# uhf_real_control_v2.net
KiCad netlist of a schematic drawn in EAGLE
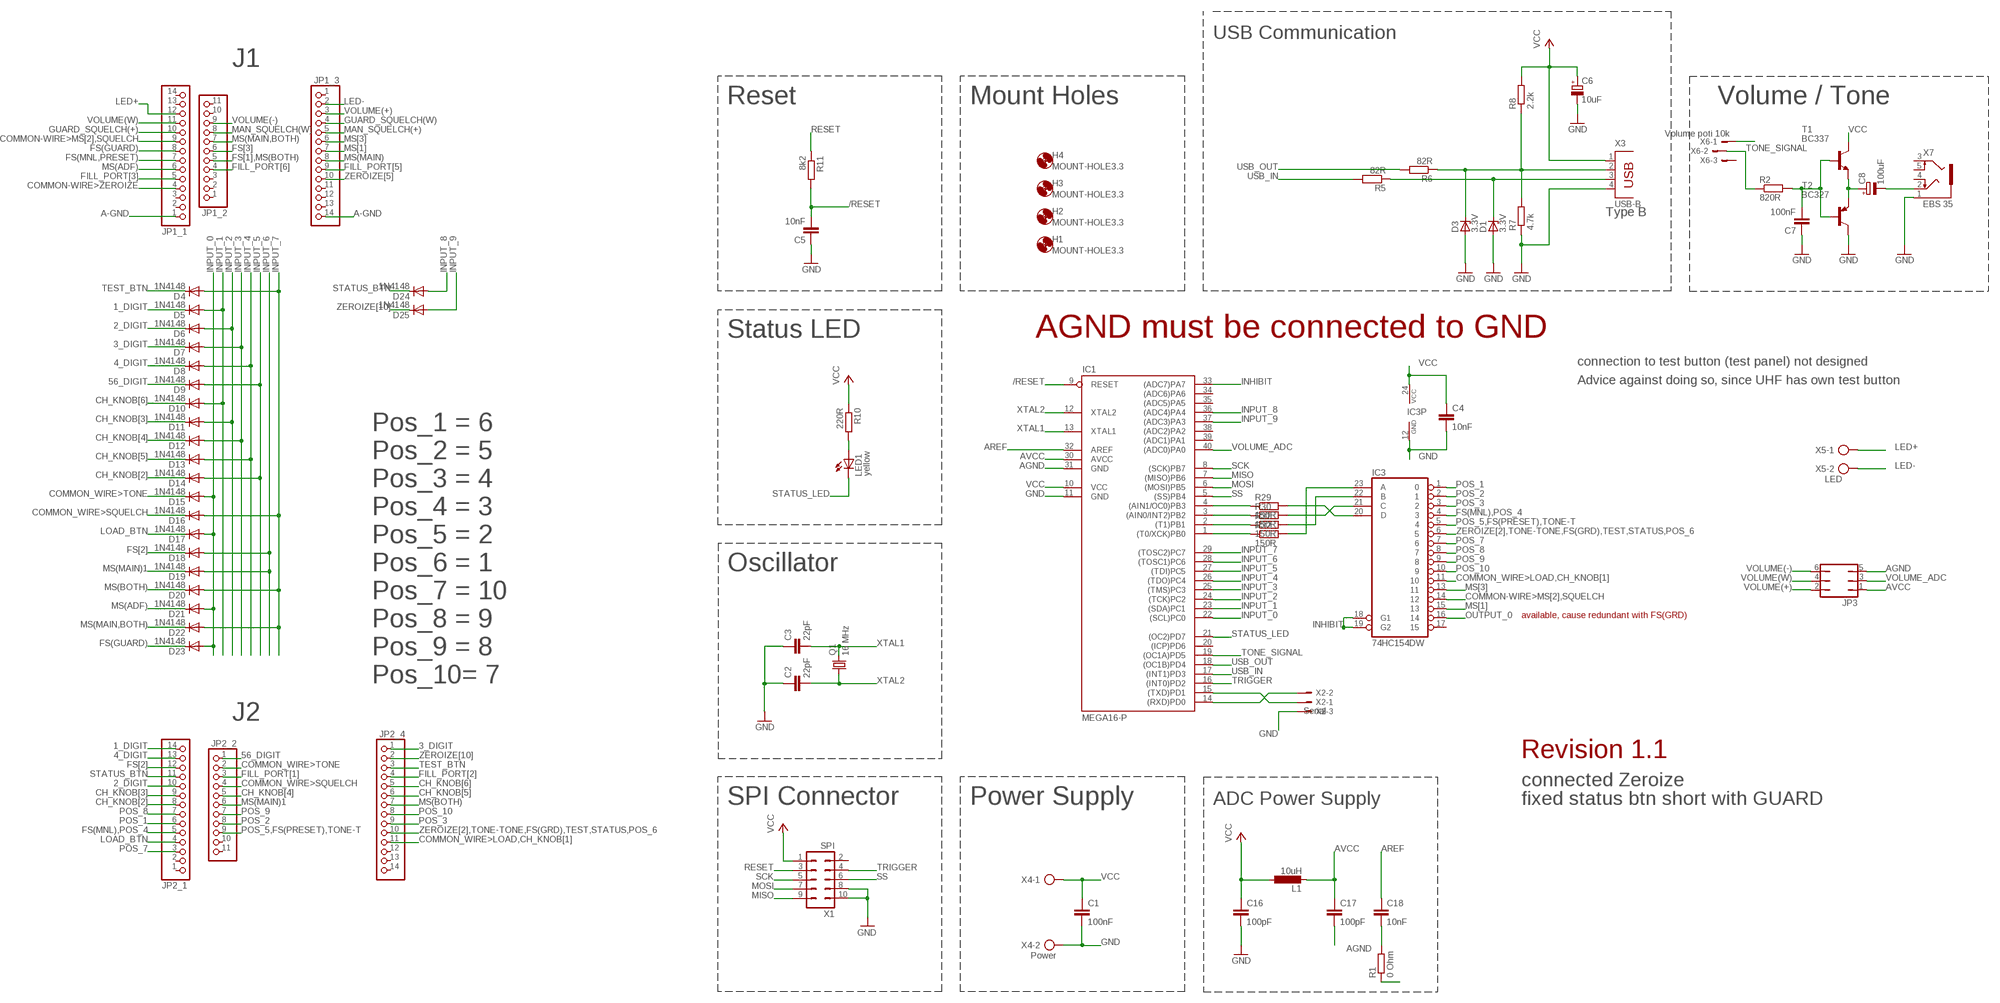
[diagram p0: schematic, sheet 1]

(export (version "E")
  (design (tool "Eeschema 10.0.6"))
  (components
    (comp (ref "C1")
      (value "100nF")
      (footprint "eagle-import:C050-024X044")
      (libsource (lib "eagle-import") (part "C-EU050-024X044"))
    )
    (comp (ref "C2")
      (value "22pF")
      (footprint "eagle-import:C025-025X050")
      (libsource (lib "eagle-import") (part "C-EU025-025X050"))
    )
    (comp (ref "C3")
      (value "22pF")
      (footprint "eagle-import:C025-025X050")
      (libsource (lib "eagle-import") (part "C-EU025-025X050"))
    )
    (comp (ref "C4")
      (value "10nF")
      (footprint "eagle-import:C025-025X050")
      (libsource (lib "eagle-import") (part "C-EU025-025X050"))
    )
    (comp (ref "C5")
      (value "10nF")
      (footprint "eagle-import:C025-025X050")
      (libsource (lib "eagle-import") (part "C-EU025-025X050"))
    )
    (comp (ref "C6")
      (value "10uF")
      (footprint "eagle-import:E2,5-6")
      (libsource (lib "eagle-import") (part "CPOL-EUE2.5-6"))
    )
    (comp (ref "C7")
      (value "100nF")
      (footprint "eagle-import:C050-024X044")
      (libsource (lib "eagle-import") (part "C-EU050-024X044"))
    )
    (comp (ref "C8")
      (value "100uF")
      (footprint "eagle-import:E2,5-6")
      (libsource (lib "eagle-import") (part "CPOL-EUE2.5-6"))
    )
    (comp (ref "C16")
      (value "100pF")
      (footprint "eagle-import:C025-025X050")
      (libsource (lib "eagle-import") (part "C-EU025-025X050"))
    )
    (comp (ref "C17")
      (value "100pF")
      (footprint "eagle-import:C025-025X050")
      (libsource (lib "eagle-import") (part "C-EU025-025X050"))
    )
    (comp (ref "C18")
      (value "10nF")
      (footprint "eagle-import:C025-025X050")
      (libsource (lib "eagle-import") (part "C-EU025-025X050"))
    )
    (comp (ref "D1")
      (value "3.3V")
      (footprint "eagle-import:DO35Z10")
      (libsource (lib "eagle-import") (part "ZENER-DIODEDO35Z10"))
    )
    (comp (ref "D3")
      (value "3.3V")
      (footprint "eagle-import:DO35Z10")
      (libsource (lib "eagle-import") (part "ZENER-DIODEDO35Z10"))
    )
    (comp (ref "D4")
      (value "1N4148")
      (footprint "eagle-import:MINIMELF")
      (libsource (lib "eagle-import") (part "DIODE-MINIMELF"))
    )
    (comp (ref "D5")
      (value "1N4148")
      (footprint "eagle-import:MINIMELF")
      (libsource (lib "eagle-import") (part "DIODE-MINIMELF"))
    )
    (comp (ref "D6")
      (value "1N4148")
      (footprint "eagle-import:MINIMELF")
      (libsource (lib "eagle-import") (part "DIODE-MINIMELF"))
    )
    (comp (ref "D7")
      (value "1N4148")
      (footprint "eagle-import:MINIMELF")
      (libsource (lib "eagle-import") (part "DIODE-MINIMELF"))
    )
    (comp (ref "D8")
      (value "1N4148")
      (footprint "eagle-import:MINIMELF")
      (libsource (lib "eagle-import") (part "DIODE-MINIMELF"))
    )
    (comp (ref "D9")
      (value "1N4148")
      (footprint "eagle-import:MINIMELF")
      (libsource (lib "eagle-import") (part "DIODE-MINIMELF"))
    )
    (comp (ref "D10")
      (value "1N4148")
      (footprint "eagle-import:MINIMELF")
      (libsource (lib "eagle-import") (part "DIODE-MINIMELF"))
    )
    (comp (ref "D11")
      (value "1N4148")
      (footprint "eagle-import:MINIMELF")
      (libsource (lib "eagle-import") (part "DIODE-MINIMELF"))
    )
    (comp (ref "D12")
      (value "1N4148")
      (footprint "eagle-import:MINIMELF")
      (libsource (lib "eagle-import") (part "DIODE-MINIMELF"))
    )
    (comp (ref "D13")
      (value "1N4148")
      (footprint "eagle-import:MINIMELF")
      (libsource (lib "eagle-import") (part "DIODE-MINIMELF"))
    )
    (comp (ref "D14")
      (value "1N4148")
      (footprint "eagle-import:MINIMELF")
      (libsource (lib "eagle-import") (part "DIODE-MINIMELF"))
    )
    (comp (ref "D15")
      (value "1N4148")
      (footprint "eagle-import:MINIMELF")
      (libsource (lib "eagle-import") (part "DIODE-MINIMELF"))
    )
    (comp (ref "D16")
      (value "1N4148")
      (footprint "eagle-import:MINIMELF")
      (libsource (lib "eagle-import") (part "DIODE-MINIMELF"))
    )
    (comp (ref "D17")
      (value "1N4148")
      (footprint "eagle-import:MINIMELF")
      (libsource (lib "eagle-import") (part "DIODE-MINIMELF"))
    )
    (comp (ref "D18")
      (value "1N4148")
      (footprint "eagle-import:MINIMELF")
      (libsource (lib "eagle-import") (part "DIODE-MINIMELF"))
    )
    (comp (ref "D19")
      (value "1N4148")
      (footprint "eagle-import:MINIMELF")
      (libsource (lib "eagle-import") (part "DIODE-MINIMELF"))
    )
    (comp (ref "D20")
      (value "1N4148")
      (footprint "eagle-import:MINIMELF")
      (libsource (lib "eagle-import") (part "DIODE-MINIMELF"))
    )
    (comp (ref "D21")
      (value "1N4148")
      (footprint "eagle-import:MINIMELF")
      (libsource (lib "eagle-import") (part "DIODE-MINIMELF"))
    )
    (comp (ref "D22")
      (value "1N4148")
      (footprint "eagle-import:MINIMELF")
      (libsource (lib "eagle-import") (part "DIODE-MINIMELF"))
    )
    (comp (ref "D23")
      (value "1N4148")
      (footprint "eagle-import:MINIMELF")
      (libsource (lib "eagle-import") (part "DIODE-MINIMELF"))
    )
    (comp (ref "D24")
      (value "1N4148")
      (footprint "eagle-import:MINIMELF")
      (libsource (lib "eagle-import") (part "DIODE-MINIMELF"))
    )
    (comp (ref "D25")
      (value "1N4148")
      (footprint "eagle-import:MINIMELF")
      (libsource (lib "eagle-import") (part "DIODE-MINIMELF"))
    )
    (comp (ref "H1")
      (value "MOUNT-HOLE3.3")
      (footprint "eagle-import:3,3")
      (libsource (lib "eagle-import") (part "MOUNT-HOLE3.3"))
    )
    (comp (ref "H2")
      (value "MOUNT-HOLE3.3")
      (footprint "eagle-import:3,3")
      (libsource (lib "eagle-import") (part "MOUNT-HOLE3.3"))
    )
    (comp (ref "H3")
      (value "MOUNT-HOLE3.3")
      (footprint "eagle-import:3,3")
      (libsource (lib "eagle-import") (part "MOUNT-HOLE3.3"))
    )
    (comp (ref "H4")
      (value "MOUNT-HOLE3.3")
      (footprint "eagle-import:3,3")
      (libsource (lib "eagle-import") (part "MOUNT-HOLE3.3"))
    )
    (comp (ref "IC1")
      (value "MEGA16-P")
      (footprint "eagle-import:DIL40")
      (libsource (lib "eagle-import") (part "MEGA16-P"))
    )
    (comp (ref "IC3")
      (value "74HC154DW")
      (footprint "eagle-import:SO24W")
      (libsource (lib "eagle-import") (part "74154DWHC"))
    )
    (comp (ref "JP1_1")
      (value "PINHD-1X14")
      (footprint "eagle-import:1X14")
      (libsource (lib "eagle-import") (part "PINHD-1X14"))
    )
    (comp (ref "JP1_2")
      (value "PINHD-1X11")
      (footprint "eagle-import:1X11")
      (libsource (lib "eagle-import") (part "PINHD-1X11"))
    )
    (comp (ref "JP1_3")
      (value "PINHD-1X14")
      (footprint "eagle-import:1X14")
      (libsource (lib "eagle-import") (part "PINHD-1X14"))
    )
    (comp (ref "JP2_1")
      (value "PINHD-1X14")
      (footprint "eagle-import:1X14")
      (libsource (lib "eagle-import") (part "PINHD-1X14"))
    )
    (comp (ref "JP2_2")
      (value "PINHD-1X11")
      (footprint "eagle-import:1X11")
      (libsource (lib "eagle-import") (part "PINHD-1X11"))
    )
    (comp (ref "JP2_4")
      (value "PINHD-1X14")
      (footprint "eagle-import:1X14")
      (libsource (lib "eagle-import") (part "PINHD-1X14"))
    )
    (comp (ref "JP3")
      (value "JP3Q")
      (footprint "eagle-import:JP3Q")
      (libsource (lib "eagle-import") (part "JP3Q"))
    )
    (comp (ref "L1")
      (value "10uH")
      (footprint "eagle-import:2200-15.24")
      (libsource (lib "eagle-import") (part "L-EU2200-15.24"))
    )
    (comp (ref "LED1")
      (value "yellow")
      (footprint "eagle-import:CHIPLED_1206")
      (libsource (lib "eagle-import") (part "LEDCHIPLED_1206"))
    )
    (comp (ref "Q1")
      (value "16 MHz")
      (footprint "eagle-import:HC18U-V")
      (libsource (lib "eagle-import") (part "CRYSTALHC18U-V"))
    )
    (comp (ref "R1")
      (value "0 Ohm")
      (footprint "eagle-import:R0805")
      (libsource (lib "eagle-import") (part "R-EU_R0805"))
    )
    (comp (ref "R2")
      (value "820R")
      (footprint "eagle-import:0207_12")
      (libsource (lib "eagle-import") (part "R-EU_0207/12"))
    )
    (comp (ref "R5")
      (value "82R")
      (footprint "eagle-import:R0805")
      (libsource (lib "eagle-import") (part "R-EU_R0805"))
    )
    (comp (ref "R6")
      (value "82R")
      (footprint "eagle-import:R0805")
      (libsource (lib "eagle-import") (part "R-EU_R0805"))
    )
    (comp (ref "R7")
      (value "4.7k")
      (footprint "eagle-import:R0805")
      (libsource (lib "eagle-import") (part "R-EU_R0805"))
    )
    (comp (ref "R8")
      (value "2.2k")
      (footprint "eagle-import:R0805")
      (libsource (lib "eagle-import") (part "R-EU_R0805"))
    )
    (comp (ref "R10")
      (value "220R")
      (footprint "eagle-import:R0805")
      (libsource (lib "eagle-import") (part "R-EU_R0805"))
    )
    (comp (ref "R11")
      (value "8k2")
      (footprint "eagle-import:M0805")
      (libsource (lib "eagle-import") (part "R-EU_M0805"))
    )
    (comp (ref "R29")
      (value "150R")
      (footprint "eagle-import:M0805")
      (libsource (lib "eagle-import") (part "R-EU_M0805"))
    )
    (comp (ref "R30")
      (value "150R")
      (footprint "eagle-import:M0805")
      (libsource (lib "eagle-import") (part "R-EU_M0805"))
    )
    (comp (ref "R31")
      (value "150R")
      (footprint "eagle-import:M0805")
      (libsource (lib "eagle-import") (part "R-EU_M0805"))
    )
    (comp (ref "R32")
      (value "150R")
      (footprint "eagle-import:M0805")
      (libsource (lib "eagle-import") (part "R-EU_M0805"))
    )
    (comp (ref "T1")
      (value "BC337")
      (footprint "eagle-import:TO92-EBC")
      (libsource (lib "eagle-import") (part "-NPN-TO92-EBCBC337-25"))
    )
    (comp (ref "T2")
      (value "BC327")
      (footprint "eagle-import:TO92-EBC")
      (libsource (lib "eagle-import") (part "-PNP-TO92-EBCBC327-25"))
    )
    (comp (ref "X1")
      (value "SPI")
      (footprint "eagle-import:ML10")
      (libsource (lib "eagle-import") (part "ML10"))
    )
    (comp (ref "X2")
      (value "Serial")
      (footprint "eagle-import:22-23-2031")
      (fields (field (name "MF") "MOLEX") (field (name "MPN") "22-23-2031"))
      (libsource (lib "eagle-import") (part "22-23-2031"))
    )
    (comp (ref "X3")
      (value "USB-B")
      (footprint "eagle-import:PN61729")
      (libsource (lib "eagle-import") (part "PN61729"))
    )
    (comp (ref "X4")
      (value "Power")
      (footprint "eagle-import:AK500_2")
      (libsource (lib "eagle-import") (part "AK500/2"))
    )
    (comp (ref "X5")
      (value "LED")
      (footprint "eagle-import:AK500_2")
      (libsource (lib "eagle-import") (part "AK500/2"))
    )
    (comp (ref "X6")
      (value "Volume poti 10k")
      (footprint "eagle-import:22-23-2031")
      (fields (field (name "MF") "MOLEX") (field (name "MPN") "22-23-2031"))
      (libsource (lib "eagle-import") (part "22-23-2031"))
    )
    (comp (ref "X7")
      (value "EBS 35")
      (footprint "eagle-import:1503_09")
      (libsource (lib "eagle-import") (part "1503_09"))
    )
  )
  (nets
    (net (code "1") (name "/1_DIGIT") (class "Default")
      (node (ref "D5") (pin "C") (pinfunction "C_C") (pintype "passive"))
      (node (ref "JP2_1") (pin "14") (pinfunction "14_14") (pintype "passive"))
    )
    (net (code "2") (name "/2_DIGIT") (class "Default")
      (node (ref "D6") (pin "C") (pinfunction "C_C") (pintype "passive"))
      (node (ref "JP2_1") (pin "10") (pinfunction "10_10") (pintype "passive"))
    )
    (net (code "3") (name "/3_DIGIT") (class "Default")
      (node (ref "D7") (pin "C") (pinfunction "C_C") (pintype "passive"))
      (node (ref "JP2_4") (pin "1") (pinfunction "1_1") (pintype "passive"))
    )
    (net (code "4") (name "/4_DIGIT") (class "Default")
      (node (ref "D8") (pin "C") (pinfunction "C_C") (pintype "passive"))
      (node (ref "JP2_1") (pin "13") (pinfunction "13_13") (pintype "passive"))
    )
    (net (code "5") (name "/56_DIGIT") (class "Default")
      (node (ref "D9") (pin "C") (pinfunction "C_C") (pintype "passive"))
      (node (ref "JP2_2") (pin "1") (pinfunction "1_1") (pintype "passive"))
    )
    (net (code "6") (name "/A-GND") (class "Default")
      (node (ref "JP1_1") (pin "1") (pinfunction "1_1") (pintype "passive"))
      (node (ref "JP1_3") (pin "14") (pinfunction "14_14") (pintype "passive"))
    )
    (net (code "7") (name "/AGND") (class "Default")
      (node (ref "C17") (pin "2") (pinfunction "2_2") (pintype "passive"))
      (node (ref "C18") (pin "2") (pinfunction "2_2") (pintype "passive"))
      (node (ref "IC1") (pin "31") (pinfunction "GND_31") (pintype "power_in"))
      (node (ref "JP3") (pin "5") (pinfunction "5_5") (pintype "passive"))
      (node (ref "R1") (pin "2") (pinfunction "2_2") (pintype "passive"))
    )
    (net (code "8") (name "/AREF") (class "Default")
      (node (ref "C18") (pin "1") (pinfunction "1_1") (pintype "passive"))
      (node (ref "IC1") (pin "32") (pinfunction "AREF_32") (pintype "passive"))
    )
    (net (code "9") (name "/AVCC") (class "Default")
      (node (ref "C17") (pin "1") (pinfunction "1_1") (pintype "passive"))
      (node (ref "IC1") (pin "30") (pinfunction "AVCC_30") (pintype "power_in"))
      (node (ref "JP3") (pin "1") (pinfunction "1_1") (pintype "passive"))
      (node (ref "L1") (pin "2") (pinfunction "2_2") (pintype "passive"))
    )
    (net (code "10") (name "/CH_KNOB[2]") (class "Default")
      (node (ref "D14") (pin "C") (pinfunction "C_C") (pintype "passive"))
      (node (ref "JP2_1") (pin "8") (pinfunction "8_8") (pintype "passive"))
    )
    (net (code "11") (name "/CH_KNOB[3]") (class "Default")
      (node (ref "D11") (pin "C") (pinfunction "C_C") (pintype "passive"))
      (node (ref "JP2_1") (pin "9") (pinfunction "9_9") (pintype "passive"))
    )
    (net (code "12") (name "/CH_KNOB[4]") (class "Default")
      (node (ref "D12") (pin "C") (pinfunction "C_C") (pintype "passive"))
      (node (ref "JP2_2") (pin "5") (pinfunction "5_5") (pintype "passive"))
    )
    (net (code "13") (name "/CH_KNOB[5]") (class "Default")
      (node (ref "D13") (pin "C") (pinfunction "C_C") (pintype "passive"))
      (node (ref "JP2_4") (pin "6") (pinfunction "6_6") (pintype "passive"))
    )
    (net (code "14") (name "/CH_KNOB[6]") (class "Default")
      (node (ref "D10") (pin "C") (pinfunction "C_C") (pintype "passive"))
      (node (ref "JP2_4") (pin "5") (pinfunction "5_5") (pintype "passive"))
    )
    (net (code "15") (name "/COMMON-WIRE>MS[2],SQUELCH") (class "Default")
      (node (ref "IC3") (pin "14") (pinfunction "12_14") (pintype "output"))
      (node (ref "JP1_1") (pin "9") (pinfunction "9_9") (pintype "passive"))
    )
    (net (code "16") (name "/COMMON-WIRE>ZEROIZE") (class "Default")
      (node (ref "JP1_1") (pin "4") (pinfunction "4_4") (pintype "passive"))
    )
    (net (code "17") (name "/COMMON_WIRE>LOAD,CH_KNOB[1]") (class "Default")
      (node (ref "IC3") (pin "11") (pinfunction "10_11") (pintype "output"))
      (node (ref "JP2_4") (pin "11") (pinfunction "11_11") (pintype "passive"))
    )
    (net (code "18") (name "/COMMON_WIRE>SQUELCH") (class "Default")
      (node (ref "D16") (pin "C") (pinfunction "C_C") (pintype "passive"))
      (node (ref "JP2_2") (pin "4") (pinfunction "4_4") (pintype "passive"))
    )
    (net (code "19") (name "/COMMON_WIRE>TONE") (class "Default")
      (node (ref "D15") (pin "C") (pinfunction "C_C") (pintype "passive"))
      (node (ref "JP2_2") (pin "2") (pinfunction "2_2") (pintype "passive"))
    )
    (net (code "20") (name "/FILL_PORT[1]") (class "Default")
      (node (ref "JP2_2") (pin "3") (pinfunction "3_3") (pintype "passive"))
    )
    (net (code "21") (name "/FILL_PORT[2]") (class "Default")
      (node (ref "JP2_4") (pin "4") (pinfunction "4_4") (pintype "passive"))
    )
    (net (code "22") (name "/FILL_PORT[3]") (class "Default")
      (node (ref "JP1_1") (pin "5") (pinfunction "5_5") (pintype "passive"))
    )
    (net (code "23") (name "/FILL_PORT[5]") (class "Default")
      (node (ref "JP1_3") (pin "9") (pinfunction "9_9") (pintype "passive"))
    )
    (net (code "24") (name "/FILL_PORT[6]") (class "Default")
      (node (ref "JP1_2") (pin "4") (pinfunction "4_4") (pintype "passive"))
    )
    (net (code "25") (name "/FS(GUARD)") (class "Default")
      (node (ref "D23") (pin "C") (pinfunction "C_C") (pintype "passive"))
      (node (ref "JP1_1") (pin "8") (pinfunction "8_8") (pintype "passive"))
    )
    (net (code "26") (name "/FS(MNL),POS_4") (class "Default")
      (node (ref "IC3") (pin "4") (pinfunction "3_4") (pintype "output"))
      (node (ref "JP2_1") (pin "5") (pinfunction "5_5") (pintype "passive"))
    )
    (net (code "27") (name "/FS(MNL,PRESET)") (class "Default")
      (node (ref "JP1_1") (pin "7") (pinfunction "7_7") (pintype "passive"))
    )
    (net (code "28") (name "/FS[1],MS(BOTH)") (class "Default")
      (node (ref "JP1_2") (pin "5") (pinfunction "5_5") (pintype "passive"))
    )
    (net (code "29") (name "/FS[2]") (class "Default")
      (node (ref "D18") (pin "C") (pinfunction "C_C") (pintype "passive"))
      (node (ref "JP2_1") (pin "12") (pinfunction "12_12") (pintype "passive"))
    )
    (net (code "30") (name "/FS[3]") (class "Default")
      (node (ref "JP1_2") (pin "6") (pinfunction "6_6") (pintype "passive"))
    )
    (net (code "31") (name "/GUARD_SQUELCH(+)") (class "Default")
      (node (ref "JP1_1") (pin "10") (pinfunction "10_10") (pintype "passive"))
    )
    (net (code "32") (name "/GUARD_SQUELCH(W)") (class "Default")
      (node (ref "JP1_3") (pin "4") (pinfunction "4_4") (pintype "passive"))
    )
    (net (code "33") (name "/INHIBIT") (class "Default")
      (node (ref "IC1") (pin "33") (pinfunction "(ADC7)PA7_33") (pintype "bidirectional"))
      (node (ref "IC3") (pin "18") (pinfunction "G1_18") (pintype "input"))
      (node (ref "IC3") (pin "19") (pinfunction "G2_19") (pintype "input"))
    )
    (net (code "34") (name "/INPUT_0") (class "Default")
      (node (ref "D15") (pin "A") (pinfunction "A_A") (pintype "passive"))
      (node (ref "D17") (pin "A") (pinfunction "A_A") (pintype "passive"))
      (node (ref "D21") (pin "A") (pinfunction "A_A") (pintype "passive"))
      (node (ref "D23") (pin "A") (pinfunction "A_A") (pintype "passive"))
      (node (ref "IC1") (pin "22") (pinfunction "(SCL)PC0_22") (pintype "bidirectional"))
    )
    (net (code "35") (name "/INPUT_1") (class "Default")
      (node (ref "D10") (pin "A") (pinfunction "A_A") (pintype "passive"))
      (node (ref "D5") (pin "A") (pinfunction "A_A") (pintype "passive"))
      (node (ref "IC1") (pin "23") (pinfunction "(SDA)PC1_23") (pintype "bidirectional"))
    )
    (net (code "36") (name "/INPUT_2") (class "Default")
      (node (ref "D11") (pin "A") (pinfunction "A_A") (pintype "passive"))
      (node (ref "D6") (pin "A") (pinfunction "A_A") (pintype "passive"))
      (node (ref "IC1") (pin "24") (pinfunction "(TCK)PC2_24") (pintype "bidirectional"))
    )
    (net (code "37") (name "/INPUT_3") (class "Default")
      (node (ref "D12") (pin "A") (pinfunction "A_A") (pintype "passive"))
      (node (ref "D7") (pin "A") (pinfunction "A_A") (pintype "passive"))
      (node (ref "IC1") (pin "25") (pinfunction "(TMS)PC3_25") (pintype "bidirectional"))
    )
    (net (code "38") (name "/INPUT_4") (class "Default")
      (node (ref "D13") (pin "A") (pinfunction "A_A") (pintype "passive"))
      (node (ref "D8") (pin "A") (pinfunction "A_A") (pintype "passive"))
      (node (ref "IC1") (pin "26") (pinfunction "(TDO)PC4_26") (pintype "bidirectional"))
    )
    (net (code "39") (name "/INPUT_5") (class "Default")
      (node (ref "D14") (pin "A") (pinfunction "A_A") (pintype "passive"))
      (node (ref "D9") (pin "A") (pinfunction "A_A") (pintype "passive"))
      (node (ref "IC1") (pin "27") (pinfunction "(TDI)PC5_27") (pintype "bidirectional"))
    )
    (net (code "40") (name "/INPUT_6") (class "Default")
      (node (ref "D18") (pin "A") (pinfunction "A_A") (pintype "passive"))
      (node (ref "D19") (pin "A") (pinfunction "A_A") (pintype "passive"))
      (node (ref "IC1") (pin "28") (pinfunction "(TOSC1)PC6_28") (pintype "bidirectional"))
    )
    (net (code "41") (name "/INPUT_7") (class "Default")
      (node (ref "D16") (pin "A") (pinfunction "A_A") (pintype "passive"))
      (node (ref "D20") (pin "A") (pinfunction "A_A") (pintype "passive"))
      (node (ref "D22") (pin "A") (pinfunction "A_A") (pintype "passive"))
      (node (ref "D4") (pin "A") (pinfunction "A_A") (pintype "passive"))
      (node (ref "IC1") (pin "29") (pinfunction "(TOSC2)PC7_29") (pintype "bidirectional"))
    )
    (net (code "42") (name "/INPUT_8") (class "Default")
      (node (ref "D24") (pin "A") (pinfunction "A_A") (pintype "passive"))
      (node (ref "IC1") (pin "36") (pinfunction "(ADC4)PA4_36") (pintype "bidirectional"))
    )
    (net (code "43") (name "/INPUT_9") (class "Default")
      (node (ref "D25") (pin "A") (pinfunction "A_A") (pintype "passive"))
      (node (ref "IC1") (pin "37") (pinfunction "(ADC3)PA3_37") (pintype "bidirectional"))
    )
    (net (code "44") (name "/LED+") (class "Default")
      (node (ref "JP1_1") (pin "12") (pinfunction "12_12") (pintype "passive"))
      (node (ref "X5") (pin "1") (pinfunction "KL_1") (pintype "passive"))
    )
    (net (code "45") (name "/LED-") (class "Default")
      (node (ref "JP1_3") (pin "2") (pinfunction "2_2") (pintype "passive"))
      (node (ref "X5") (pin "2") (pinfunction "KL_2") (pintype "passive"))
    )
    (net (code "46") (name "/LOAD_BTN") (class "Default")
      (node (ref "D17") (pin "C") (pinfunction "C_C") (pintype "passive"))
      (node (ref "JP2_1") (pin "4") (pinfunction "4_4") (pintype "passive"))
    )
    (net (code "47") (name "/MAN_SQUELCH(+)") (class "Default")
      (node (ref "JP1_3") (pin "5") (pinfunction "5_5") (pintype "passive"))
    )
    (net (code "48") (name "/MAN_SQUELCH(W)") (class "Default")
      (node (ref "JP1_2") (pin "8") (pinfunction "8_8") (pintype "passive"))
    )
    (net (code "49") (name "/MISO") (class "Default")
      (node (ref "IC1") (pin "7") (pinfunction "(MISO)PB6_7") (pintype "bidirectional"))
      (node (ref "X1") (pin "9") (pinfunction "9_9") (pintype "passive"))
    )
    (net (code "50") (name "/MOSI") (class "Default")
      (node (ref "IC1") (pin "6") (pinfunction "(MOSI)PB5_6") (pintype "bidirectional"))
      (node (ref "X1") (pin "7") (pinfunction "7_7") (pintype "passive"))
    )
    (net (code "51") (name "/MS(ADF)") (class "Default")
      (node (ref "D21") (pin "C") (pinfunction "C_C") (pintype "passive"))
      (node (ref "JP1_1") (pin "6") (pinfunction "6_6") (pintype "passive"))
    )
    (net (code "52") (name "/MS(BOTH)") (class "Default")
      (node (ref "D20") (pin "C") (pinfunction "C_C") (pintype "passive"))
      (node (ref "JP2_4") (pin "7") (pinfunction "7_7") (pintype "passive"))
    )
    (net (code "53") (name "/MS(MAIN)") (class "Default")
      (node (ref "JP1_3") (pin "8") (pinfunction "8_8") (pintype "passive"))
    )
    (net (code "54") (name "/MS(MAIN)1") (class "Default")
      (node (ref "D19") (pin "C") (pinfunction "C_C") (pintype "passive"))
      (node (ref "JP2_2") (pin "6") (pinfunction "6_6") (pintype "passive"))
    )
    (net (code "55") (name "/MS(MAIN,BOTH)") (class "Default")
      (node (ref "D22") (pin "C") (pinfunction "C_C") (pintype "passive"))
      (node (ref "JP1_2") (pin "7") (pinfunction "7_7") (pintype "passive"))
    )
    (net (code "56") (name "/MS[1]") (class "Default")
      (node (ref "IC3") (pin "15") (pinfunction "13_15") (pintype "output"))
      (node (ref "JP1_3") (pin "7") (pinfunction "7_7") (pintype "passive"))
    )
    (net (code "57") (name "/MS[3]") (class "Default")
      (node (ref "IC3") (pin "13") (pinfunction "11_13") (pintype "output"))
      (node (ref "JP1_3") (pin "6") (pinfunction "6_6") (pintype "passive"))
    )
    (net (code "58") (name "/OUTPUT_0") (class "Default")
      (node (ref "IC3") (pin "16") (pinfunction "14_16") (pintype "output"))
    )
    (net (code "59") (name "/POS_1") (class "Default")
      (node (ref "IC3") (pin "1") (pinfunction "0_1") (pintype "output"))
      (node (ref "JP2_1") (pin "6") (pinfunction "6_6") (pintype "passive"))
    )
    (net (code "60") (name "/POS_2") (class "Default")
      (node (ref "IC3") (pin "2") (pinfunction "1_2") (pintype "output"))
      (node (ref "JP2_2") (pin "8") (pinfunction "8_8") (pintype "passive"))
    )
    (net (code "61") (name "/POS_3") (class "Default")
      (node (ref "IC3") (pin "3") (pinfunction "2_3") (pintype "output"))
      (node (ref "JP2_4") (pin "9") (pinfunction "9_9") (pintype "passive"))
    )
    (net (code "62") (name "/POS_5,FS(PRESET),TONE-T") (class "Default")
      (node (ref "IC3") (pin "5") (pinfunction "4_5") (pintype "output"))
      (node (ref "JP2_2") (pin "9") (pinfunction "9_9") (pintype "passive"))
    )
    (net (code "63") (name "/POS_7") (class "Default")
      (node (ref "IC3") (pin "7") (pinfunction "6_7") (pintype "output"))
      (node (ref "JP2_1") (pin "3") (pinfunction "3_3") (pintype "passive"))
    )
    (net (code "64") (name "/POS_8") (class "Default")
      (node (ref "IC3") (pin "8") (pinfunction "7_8") (pintype "output"))
      (node (ref "JP2_1") (pin "7") (pinfunction "7_7") (pintype "passive"))
    )
    (net (code "65") (name "/POS_9") (class "Default")
      (node (ref "IC3") (pin "9") (pinfunction "8_9") (pintype "output"))
      (node (ref "JP2_2") (pin "7") (pinfunction "7_7") (pintype "passive"))
    )
    (net (code "66") (name "/POS_10") (class "Default")
      (node (ref "IC3") (pin "10") (pinfunction "9_10") (pintype "output"))
      (node (ref "JP2_4") (pin "8") (pinfunction "8_8") (pintype "passive"))
    )
    (net (code "67") (name "/RESET") (class "Default")
      (node (ref "R11") (pin "1") (pinfunction "1_1") (pintype "passive"))
      (node (ref "X1") (pin "3") (pinfunction "3_3") (pintype "passive"))
    )
    (net (code "68") (name "/SCK") (class "Default")
      (node (ref "IC1") (pin "8") (pinfunction "(SCK)PB7_8") (pintype "bidirectional"))
      (node (ref "X1") (pin "5") (pinfunction "5_5") (pintype "passive"))
    )
    (net (code "69") (name "/SS") (class "Default")
      (node (ref "IC1") (pin "5") (pinfunction "(SS)PB4_5") (pintype "bidirectional"))
      (node (ref "X1") (pin "6") (pinfunction "6_6") (pintype "passive"))
    )
    (net (code "70") (name "/STATUS_BTN") (class "Default")
      (node (ref "D24") (pin "C") (pinfunction "C_C") (pintype "passive"))
      (node (ref "JP2_1") (pin "11") (pinfunction "11_11") (pintype "passive"))
    )
    (net (code "71") (name "/STATUS_LED") (class "Default")
      (node (ref "IC1") (pin "21") (pinfunction "(OC2)PD7_21") (pintype "bidirectional"))
      (node (ref "LED1") (pin "C") (pinfunction "C_C") (pintype "passive"))
    )
    (net (code "72") (name "/TEST_BTN") (class "Default")
      (node (ref "D4") (pin "C") (pinfunction "C_C") (pintype "passive"))
      (node (ref "JP2_4") (pin "3") (pinfunction "3_3") (pintype "passive"))
    )
    (net (code "73") (name "/TONE_SIGNAL") (class "Default")
      (node (ref "IC1") (pin "19") (pinfunction "(OC1A)PD5_19") (pintype "bidirectional"))
      (node (ref "X6") (pin "1") (pinfunction "S_1") (pintype "passive"))
    )
    (net (code "74") (name "/TRIGGER") (class "Default")
      (node (ref "IC1") (pin "16") (pinfunction "(INT0)PD2_16") (pintype "bidirectional"))
      (node (ref "X1") (pin "4") (pinfunction "4_4") (pintype "passive"))
    )
    (net (code "75") (name "/USB_IN") (class "Default")
      (node (ref "IC1") (pin "17") (pinfunction "(INT1)PD3_17") (pintype "bidirectional"))
      (node (ref "R5") (pin "2") (pinfunction "2_2") (pintype "passive"))
    )
    (net (code "76") (name "/USB_OUT") (class "Default")
      (node (ref "IC1") (pin "18") (pinfunction "(OC1B)PD4_18") (pintype "bidirectional"))
      (node (ref "R6") (pin "2") (pinfunction "2_2") (pintype "passive"))
    )
    (net (code "77") (name "/VOLUME(+)") (class "Default")
      (node (ref "JP1_3") (pin "3") (pinfunction "3_3") (pintype "passive"))
      (node (ref "JP3") (pin "2") (pinfunction "2_2") (pintype "passive"))
    )
    (net (code "78") (name "/VOLUME(-)") (class "Default")
      (node (ref "JP1_2") (pin "9") (pinfunction "9_9") (pintype "passive"))
      (node (ref "JP3") (pin "6") (pinfunction "6_6") (pintype "passive"))
    )
    (net (code "79") (name "/VOLUME(W)") (class "Default")
      (node (ref "JP1_1") (pin "11") (pinfunction "11_11") (pintype "passive"))
      (node (ref "JP3") (pin "4") (pinfunction "4_4") (pintype "passive"))
    )
    (net (code "80") (name "/VOLUME_ADC") (class "Default")
      (node (ref "IC1") (pin "40") (pinfunction "(ADC0)PA0_40") (pintype "bidirectional"))
      (node (ref "JP3") (pin "3") (pinfunction "3_3") (pintype "passive"))
    )
    (net (code "81") (name "/XTAL1") (class "Default")
      (node (ref "C3") (pin "2") (pinfunction "2_2") (pintype "passive"))
      (node (ref "IC1") (pin "13") (pinfunction "XTAL1_13") (pintype "bidirectional"))
      (node (ref "Q1") (pin "2") (pinfunction "2_2") (pintype "passive"))
    )
    (net (code "82") (name "/XTAL2") (class "Default")
      (node (ref "C2") (pin "2") (pinfunction "2_2") (pintype "passive"))
      (node (ref "IC1") (pin "12") (pinfunction "XTAL2_12") (pintype "bidirectional"))
      (node (ref "Q1") (pin "1") (pinfunction "1_1") (pintype "passive"))
    )
    (net (code "83") (name "/ZEROIZE[2],TONE-TONE,FS(GRD),TEST,STATUS,POS_6") (class "Default")
      (node (ref "IC3") (pin "6") (pinfunction "5_6") (pintype "output"))
      (node (ref "JP2_4") (pin "10") (pinfunction "10_10") (pintype "passive"))
    )
    (net (code "84") (name "/ZEROIZE[5]") (class "Default")
      (node (ref "JP1_3") (pin "10") (pinfunction "10_10") (pintype "passive"))
    )
    (net (code "85") (name "/ZEROIZE[10]") (class "Default")
      (node (ref "D25") (pin "C") (pinfunction "C_C") (pintype "passive"))
      (node (ref "JP2_4") (pin "2") (pinfunction "2_2") (pintype "passive"))
    )
    (net (code "86") (name "/{slash}RESET") (class "Default")
      (node (ref "C5") (pin "2") (pinfunction "2_2") (pintype "passive"))
      (node (ref "IC1") (pin "9") (pinfunction "RESET_9") (pintype "input"))
      (node (ref "R11") (pin "2") (pinfunction "2_2") (pintype "passive"))
    )
    (net (code "87") (name "GND") (class "Default")
      (node (ref "C1") (pin "2") (pinfunction "2_2") (pintype "passive"))
      (node (ref "C16") (pin "2") (pinfunction "2_2") (pintype "passive"))
      (node (ref "C2") (pin "1") (pinfunction "1_1") (pintype "passive"))
      (node (ref "C3") (pin "1") (pinfunction "1_1") (pintype "passive"))
      (node (ref "C4") (pin "2") (pinfunction "2_2") (pintype "passive"))
      (node (ref "C5") (pin "1") (pinfunction "1_1") (pintype "passive"))
      (node (ref "C6") (pin "-") (pinfunction "-_-") (pintype "passive"))
      (node (ref "C7") (pin "1") (pinfunction "1_1") (pintype "passive"))
      (node (ref "D1") (pin "A") (pinfunction "A_A") (pintype "passive"))
      (node (ref "D3") (pin "A") (pinfunction "A_A") (pintype "passive"))
      (node (ref "IC1") (pin "11") (pinfunction "GND_11") (pintype "power_in"))
      (node (ref "IC3") (pin "12") (pinfunction "GND_12") (pintype "power_in"))
      (node (ref "R1") (pin "1") (pinfunction "1_1") (pintype "passive"))
      (node (ref "R7") (pin "1") (pinfunction "1_1") (pintype "passive"))
      (node (ref "T2") (pin "C") (pinfunction "C_C") (pintype "passive"))
      (node (ref "X1") (pin "10") (pinfunction "10_10") (pintype "passive"))
      (node (ref "X1") (pin "8") (pinfunction "8_8") (pintype "passive"))
      (node (ref "X2") (pin "3") (pinfunction "S_3") (pintype "passive"))
      (node (ref "X3") (pin "4") (pinfunction "4_4") (pintype "passive"))
      (node (ref "X4") (pin "2") (pinfunction "KL_2") (pintype "passive"))
      (node (ref "X7") (pin "1") (pinfunction "1_1") (pintype "passive"))
    )
    (net (code "88") (name "Net-(C7-Pad2)") (class "Default")
      (node (ref "C7") (pin "2") (pinfunction "2_2") (pintype "passive"))
      (node (ref "R2") (pin "2") (pinfunction "2_2") (pintype "passive"))
      (node (ref "T1") (pin "B") (pinfunction "B_B") (pintype "passive"))
      (node (ref "T2") (pin "B") (pinfunction "B_B") (pintype "passive"))
    )
    (net (code "89") (name "Net-(C8-Pad+)") (class "Default")
      (node (ref "C8") (pin "+") (pinfunction "+_+") (pintype "passive"))
      (node (ref "T1") (pin "E") (pinfunction "E_E") (pintype "passive"))
      (node (ref "T2") (pin "E") (pinfunction "E_E") (pintype "passive"))
    )
    (net (code "90") (name "Net-(C8-Pad-)") (class "Default")
      (node (ref "C8") (pin "-") (pinfunction "-_-") (pintype "passive"))
      (node (ref "X7") (pin "2") (pinfunction "2_2") (pintype "passive"))
    )
    (net (code "91") (name "Net-(D1-PadC)") (class "Default")
      (node (ref "D1") (pin "C") (pinfunction "C_C") (pintype "passive"))
      (node (ref "R5") (pin "1") (pinfunction "1_1") (pintype "passive"))
      (node (ref "X3") (pin "3") (pinfunction "3_3") (pintype "passive"))
    )
    (net (code "92") (name "Net-(D3-PadC)") (class "Default")
      (node (ref "D3") (pin "C") (pinfunction "C_C") (pintype "passive"))
      (node (ref "R6") (pin "1") (pinfunction "1_1") (pintype "passive"))
      (node (ref "R7") (pin "2") (pinfunction "2_2") (pintype "passive"))
      (node (ref "R8") (pin "1") (pinfunction "1_1") (pintype "passive"))
      (node (ref "X3") (pin "2") (pinfunction "2_2") (pintype "passive"))
    )
    (net (code "93") (name "Net-(IC1-(AIN0{slash}INT2)PB2)") (class "Default")
      (node (ref "IC1") (pin "3") (pinfunction "(AIN0/INT2)PB2_3") (pintype "bidirectional"))
      (node (ref "R30") (pin "1") (pinfunction "1_1") (pintype "passive"))
    )
    (net (code "94") (name "Net-(IC1-(AIN1{slash}OC0)PB3)") (class "Default")
      (node (ref "IC1") (pin "4") (pinfunction "(AIN1/OC0)PB3_4") (pintype "bidirectional"))
      (node (ref "R29") (pin "1") (pinfunction "1_1") (pintype "passive"))
    )
    (net (code "95") (name "Net-(IC1-(RXD)PD0)") (class "Default")
      (node (ref "IC1") (pin "14") (pinfunction "(RXD)PD0_14") (pintype "bidirectional"))
      (node (ref "X2") (pin "2") (pinfunction "S_2") (pintype "passive"))
    )
    (net (code "96") (name "Net-(IC1-(T0{slash}XCK)PB0)") (class "Default")
      (node (ref "IC1") (pin "1") (pinfunction "(T0/XCK)PB0_1") (pintype "bidirectional"))
      (node (ref "R32") (pin "1") (pinfunction "1_1") (pintype "passive"))
    )
    (net (code "97") (name "Net-(IC1-(T1)PB1)") (class "Default")
      (node (ref "IC1") (pin "2") (pinfunction "(T1)PB1_2") (pintype "bidirectional"))
      (node (ref "R31") (pin "1") (pinfunction "1_1") (pintype "passive"))
    )
    (net (code "98") (name "Net-(IC1-(TXD)PD1)") (class "Default")
      (node (ref "IC1") (pin "15") (pinfunction "(TXD)PD1_15") (pintype "bidirectional"))
      (node (ref "X2") (pin "1") (pinfunction "S_1") (pintype "passive"))
    )
    (net (code "99") (name "Net-(IC3A-A)") (class "Default")
      (node (ref "IC3") (pin "23") (pinfunction "A_23") (pintype "input"))
      (node (ref "R32") (pin "2") (pinfunction "2_2") (pintype "passive"))
    )
    (net (code "100") (name "Net-(IC3A-B)") (class "Default")
      (node (ref "IC3") (pin "22") (pinfunction "B_22") (pintype "input"))
      (node (ref "R31") (pin "2") (pinfunction "2_2") (pintype "passive"))
    )
    (net (code "101") (name "Net-(IC3A-C)") (class "Default")
      (node (ref "IC3") (pin "21") (pinfunction "C_21") (pintype "input"))
      (node (ref "R30") (pin "2") (pinfunction "2_2") (pintype "passive"))
    )
    (net (code "102") (name "Net-(IC3A-D)") (class "Default")
      (node (ref "IC3") (pin "20") (pinfunction "D_20") (pintype "input"))
      (node (ref "R29") (pin "2") (pinfunction "2_2") (pintype "passive"))
    )
    (net (code "103") (name "Net-(LED1-PadA)") (class "Default")
      (node (ref "LED1") (pin "A") (pinfunction "A_A") (pintype "passive"))
      (node (ref "R10") (pin "2") (pinfunction "2_2") (pintype "passive"))
    )
    (net (code "104") (name "Net-(X6B-S)") (class "Default")
      (node (ref "R2") (pin "1") (pinfunction "1_1") (pintype "passive"))
      (node (ref "X6") (pin "2") (pinfunction "S_2") (pintype "passive"))
    )
    (net (code "105") (name "VCC") (class "Default")
      (node (ref "C1") (pin "1") (pinfunction "1_1") (pintype "passive"))
      (node (ref "C16") (pin "1") (pinfunction "1_1") (pintype "passive"))
      (node (ref "C4") (pin "1") (pinfunction "1_1") (pintype "passive"))
      (node (ref "C6") (pin "+") (pinfunction "+_+") (pintype "passive"))
      (node (ref "IC1") (pin "10") (pinfunction "VCC_10") (pintype "power_in"))
      (node (ref "IC3") (pin "24") (pinfunction "VCC_24") (pintype "power_in"))
      (node (ref "L1") (pin "1") (pinfunction "1_1") (pintype "passive"))
      (node (ref "R10") (pin "1") (pinfunction "1_1") (pintype "passive"))
      (node (ref "R8") (pin "2") (pinfunction "2_2") (pintype "passive"))
      (node (ref "T1") (pin "C") (pinfunction "C_C") (pintype "passive"))
      (node (ref "X1") (pin "1") (pinfunction "1_1") (pintype "passive"))
      (node (ref "X3") (pin "1") (pinfunction "1_1") (pintype "passive"))
      (node (ref "X4") (pin "1") (pinfunction "KL_1") (pintype "passive"))
    )
    (net (code "106") (name "unconnected-(IC1-(ADC1)PA1-Pad39)") (class "Default")
      (node (ref "IC1") (pin "39") (pinfunction "(ADC1)PA1_39") (pintype "bidirectional"))
    )
    (net (code "107") (name "unconnected-(IC1-(ADC2)PA2-Pad38)") (class "Default")
      (node (ref "IC1") (pin "38") (pinfunction "(ADC2)PA2_38") (pintype "bidirectional"))
    )
    (net (code "108") (name "unconnected-(IC1-(ADC5)PA5-Pad35)") (class "Default")
      (node (ref "IC1") (pin "35") (pinfunction "(ADC5)PA5_35") (pintype "bidirectional"))
    )
    (net (code "109") (name "unconnected-(IC1-(ADC6)PA6-Pad34)") (class "Default")
      (node (ref "IC1") (pin "34") (pinfunction "(ADC6)PA6_34") (pintype "bidirectional"))
    )
    (net (code "110") (name "unconnected-(IC1-(ICP)PD6-Pad20)") (class "Default")
      (node (ref "IC1") (pin "20") (pinfunction "(ICP)PD6_20") (pintype "bidirectional"))
    )
    (net (code "111") (name "unconnected-(IC3A-15-Pad17)") (class "Default")
      (node (ref "IC3") (pin "17") (pinfunction "15_17") (pintype "output"))
    )
    (net (code "112") (name "unconnected-(JP1_1-Pad2)") (class "Default")
      (node (ref "JP1_1") (pin "2") (pinfunction "2_2") (pintype "passive"))
    )
    (net (code "113") (name "unconnected-(JP1_1-Pad3)") (class "Default")
      (node (ref "JP1_1") (pin "3") (pinfunction "3_3") (pintype "passive"))
    )
    (net (code "114") (name "unconnected-(JP1_1-Pad13)") (class "Default")
      (node (ref "JP1_1") (pin "13") (pinfunction "13_13") (pintype "passive"))
    )
    (net (code "115") (name "unconnected-(JP1_1-Pad14)") (class "Default")
      (node (ref "JP1_1") (pin "14") (pinfunction "14_14") (pintype "passive"))
    )
    (net (code "116") (name "unconnected-(JP1_2-Pad1)") (class "Default")
      (node (ref "JP1_2") (pin "1") (pinfunction "1_1") (pintype "passive"))
    )
    (net (code "117") (name "unconnected-(JP1_2-Pad2)") (class "Default")
      (node (ref "JP1_2") (pin "2") (pinfunction "2_2") (pintype "passive"))
    )
    (net (code "118") (name "unconnected-(JP1_2-Pad3)") (class "Default")
      (node (ref "JP1_2") (pin "3") (pinfunction "3_3") (pintype "passive"))
    )
    (net (code "119") (name "unconnected-(JP1_2-Pad10)") (class "Default")
      (node (ref "JP1_2") (pin "10") (pinfunction "10_10") (pintype "passive"))
    )
    (net (code "120") (name "unconnected-(JP1_2-Pad11)") (class "Default")
      (node (ref "JP1_2") (pin "11") (pinfunction "11_11") (pintype "passive"))
    )
    (net (code "121") (name "unconnected-(JP1_3-Pad1)") (class "Default")
      (node (ref "JP1_3") (pin "1") (pinfunction "1_1") (pintype "passive"))
    )
    (net (code "122") (name "unconnected-(JP1_3-Pad11)") (class "Default")
      (node (ref "JP1_3") (pin "11") (pinfunction "11_11") (pintype "passive"))
    )
    (net (code "123") (name "unconnected-(JP1_3-Pad12)") (class "Default")
      (node (ref "JP1_3") (pin "12") (pinfunction "12_12") (pintype "passive"))
    )
    (net (code "124") (name "unconnected-(JP1_3-Pad13)") (class "Default")
      (node (ref "JP1_3") (pin "13") (pinfunction "13_13") (pintype "passive"))
    )
    (net (code "125") (name "unconnected-(JP2_1-Pad1)") (class "Default")
      (node (ref "JP2_1") (pin "1") (pinfunction "1_1") (pintype "passive"))
    )
    (net (code "126") (name "unconnected-(JP2_1-Pad2)") (class "Default")
      (node (ref "JP2_1") (pin "2") (pinfunction "2_2") (pintype "passive"))
    )
    (net (code "127") (name "unconnected-(JP2_2-Pad10)") (class "Default")
      (node (ref "JP2_2") (pin "10") (pinfunction "10_10") (pintype "passive"))
    )
    (net (code "128") (name "unconnected-(JP2_2-Pad11)") (class "Default")
      (node (ref "JP2_2") (pin "11") (pinfunction "11_11") (pintype "passive"))
    )
    (net (code "129") (name "unconnected-(JP2_4-Pad12)") (class "Default")
      (node (ref "JP2_4") (pin "12") (pinfunction "12_12") (pintype "passive"))
    )
    (net (code "130") (name "unconnected-(JP2_4-Pad13)") (class "Default")
      (node (ref "JP2_4") (pin "13") (pinfunction "13_13") (pintype "passive"))
    )
    (net (code "131") (name "unconnected-(JP2_4-Pad14)") (class "Default")
      (node (ref "JP2_4") (pin "14") (pinfunction "14_14") (pintype "passive"))
    )
    (net (code "132") (name "unconnected-(X1-Pad2)") (class "Default")
      (node (ref "X1") (pin "2") (pinfunction "2_2") (pintype "passive"))
    )
    (net (code "133") (name "unconnected-(X6C-S-Pad3)") (class "Default")
      (node (ref "X6") (pin "3") (pinfunction "S_3") (pintype "passive"))
    )
    (net (code "134") (name "unconnected-(X7-Pad3)") (class "Default")
      (node (ref "X7") (pin "3") (pinfunction "3_3") (pintype "passive"))
    )
    (net (code "135") (name "unconnected-(X7-Pad4)") (class "Default")
      (node (ref "X7") (pin "4") (pinfunction "4_4") (pintype "passive"))
    )
    (net (code "136") (name "unconnected-(X7-Pad5)") (class "Default")
      (node (ref "X7") (pin "5") (pinfunction "5_5") (pintype "passive"))
    )
  )
)
